# micro-board.net
KiCad netlist of a schematic drawn in EAGLE
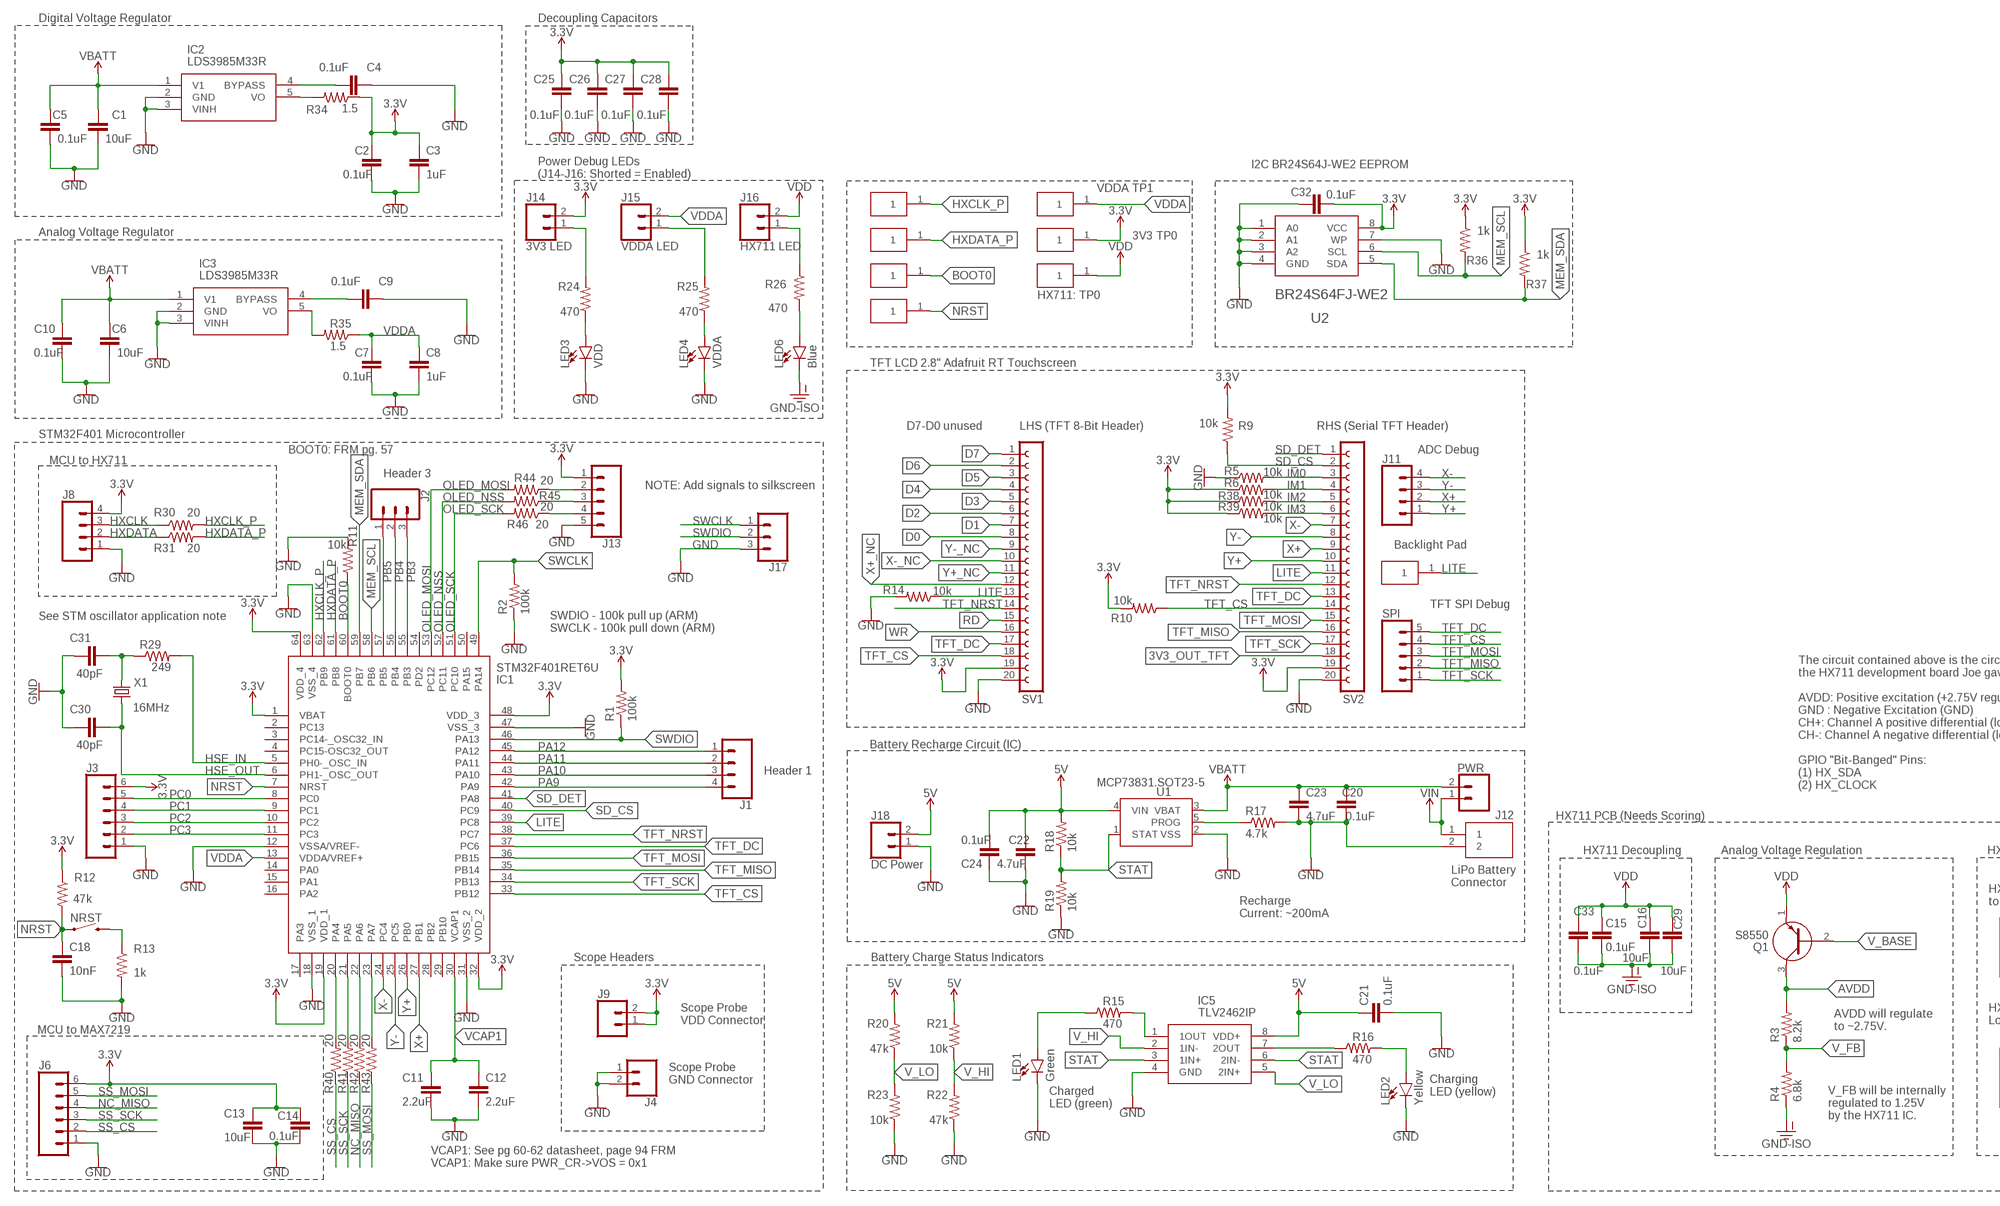
[diagram p0: schematic, sheet 1, part 1 of 2]
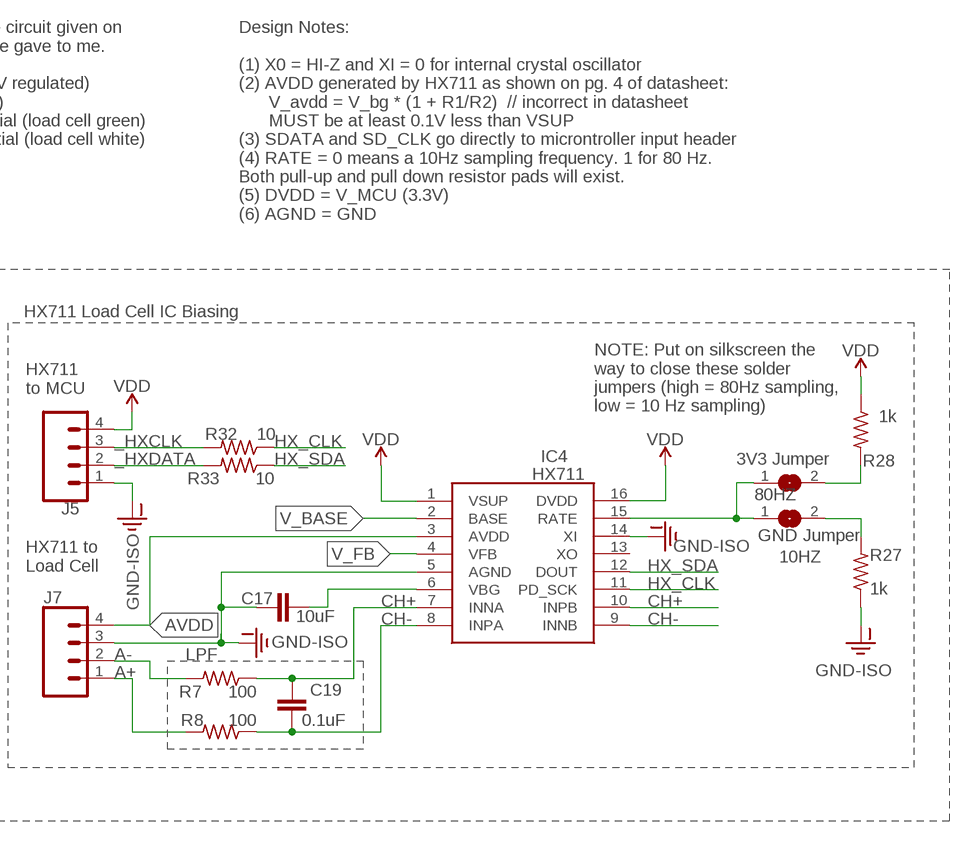
[diagram p1: schematic, sheet 1, part 2 of 2]

(export (version "E")
  (design (tool "Eeschema 10.0.6"))
  (components
    (comp (ref "10HZ")
      (value "GND Jumper")
      (footprint "eagle-import:SJ")
      (libsource (lib "eagle-import") (part "SJ"))
    )
    (comp (ref "80HZ")
      (value "3V3 Jumper")
      (footprint "eagle-import:SJ")
      (libsource (lib "eagle-import") (part "SJ"))
    )
    (comp (ref "C1")
      (value "10uF")
      (footprint "eagle-import:C0603")
      (libsource (lib "eagle-import") (part "CAPACITOR0603"))
    )
    (comp (ref "C2")
      (value "0.1uF")
      (footprint "eagle-import:C0603")
      (libsource (lib "eagle-import") (part "CAPACITOR0603"))
    )
    (comp (ref "C3")
      (value "1uF")
      (footprint "eagle-import:C0603")
      (libsource (lib "eagle-import") (part "CAPACITOR0603"))
    )
    (comp (ref "C4")
      (value "0.1uF")
      (footprint "eagle-import:C0603")
      (libsource (lib "eagle-import") (part "CAPACITOR0603"))
    )
    (comp (ref "C5")
      (value "0.1uF")
      (footprint "eagle-import:C0603")
      (libsource (lib "eagle-import") (part "CAPACITOR0603"))
    )
    (comp (ref "C6")
      (value "10uF")
      (footprint "eagle-import:C0603")
      (libsource (lib "eagle-import") (part "CAPACITOR0603"))
    )
    (comp (ref "C7")
      (value "0.1uF")
      (footprint "eagle-import:C0603")
      (libsource (lib "eagle-import") (part "CAPACITOR0603"))
    )
    (comp (ref "C8")
      (value "1uF")
      (footprint "eagle-import:C0603")
      (libsource (lib "eagle-import") (part "CAPACITOR0603"))
    )
    (comp (ref "C9")
      (value "0.1uF")
      (footprint "eagle-import:C0603")
      (libsource (lib "eagle-import") (part "CAPACITOR0603"))
    )
    (comp (ref "C10")
      (value "0.1uF")
      (footprint "eagle-import:C0603")
      (libsource (lib "eagle-import") (part "CAPACITOR0603"))
    )
    (comp (ref "C11")
      (value "2.2uF")
      (footprint "eagle-import:C0603")
      (libsource (lib "eagle-import") (part "CAPACITOR0603"))
    )
    (comp (ref "C12")
      (value "2.2uF")
      (footprint "eagle-import:C0603")
      (libsource (lib "eagle-import") (part "CAPACITOR0603"))
    )
    (comp (ref "C13")
      (value "10uF")
      (footprint "eagle-import:C0603")
      (libsource (lib "eagle-import") (part "CAPACITOR0603"))
    )
    (comp (ref "C14")
      (value "0.1uF")
      (footprint "eagle-import:C0603")
      (libsource (lib "eagle-import") (part "CAPACITOR0603"))
    )
    (comp (ref "C15")
      (value "0.1uF")
      (footprint "eagle-import:C0603")
      (libsource (lib "eagle-import") (part "CAPACITOR0603"))
    )
    (comp (ref "C16")
      (value "10uF")
      (footprint "eagle-import:C0603")
      (libsource (lib "eagle-import") (part "CAPACITOR0603"))
    )
    (comp (ref "C17")
      (value "10uF")
      (footprint "eagle-import:C0603")
      (libsource (lib "eagle-import") (part "CAPACITOR0603"))
    )
    (comp (ref "C18")
      (value "10nF")
      (footprint "eagle-import:C0603")
      (libsource (lib "eagle-import") (part "CAPACITOR0603"))
    )
    (comp (ref "C19")
      (value "0.1uF")
      (footprint "eagle-import:C0603")
      (libsource (lib "eagle-import") (part "CAPACITOR0603"))
    )
    (comp (ref "C20")
      (value "0.1uF")
      (footprint "eagle-import:C0603")
      (libsource (lib "eagle-import") (part "CAPACITOR0603"))
    )
    (comp (ref "C21")
      (value "0.1uF")
      (footprint "eagle-import:C0603")
      (libsource (lib "eagle-import") (part "CAPACITOR0603"))
    )
    (comp (ref "C22")
      (value "4.7uF")
      (footprint "eagle-import:C5B4.5")
      (libsource (lib "eagle-import") (part "C5/4.5"))
    )
    (comp (ref "C23")
      (value "4.7uF")
      (footprint "eagle-import:C5B4.5")
      (libsource (lib "eagle-import") (part "C5/4.5"))
    )
    (comp (ref "C24")
      (value "0.1uF")
      (footprint "eagle-import:C0603")
      (libsource (lib "eagle-import") (part "CAPACITOR0603"))
    )
    (comp (ref "C25")
      (value "0.1uF")
      (footprint "eagle-import:C0603")
      (libsource (lib "eagle-import") (part "CAPACITOR0603"))
    )
    (comp (ref "C26")
      (value "0.1uF")
      (footprint "eagle-import:C0603")
      (libsource (lib "eagle-import") (part "CAPACITOR0603"))
    )
    (comp (ref "C27")
      (value "0.1uF")
      (footprint "eagle-import:C0603")
      (libsource (lib "eagle-import") (part "CAPACITOR0603"))
    )
    (comp (ref "C28")
      (value "0.1uF")
      (footprint "eagle-import:C0603")
      (libsource (lib "eagle-import") (part "CAPACITOR0603"))
    )
    (comp (ref "C29")
      (value "10uF")
      (footprint "eagle-import:C0603")
      (libsource (lib "eagle-import") (part "CAPACITOR0603"))
    )
    (comp (ref "C30")
      (value "40pF")
      (footprint "eagle-import:C0603")
      (libsource (lib "eagle-import") (part "CAPACITOR0603"))
    )
    (comp (ref "C31")
      (value "40pF")
      (footprint "eagle-import:C0603")
      (libsource (lib "eagle-import") (part "CAPACITOR0603"))
    )
    (comp (ref "C32")
      (value "0.1uF")
      (footprint "eagle-import:C0603")
      (libsource (lib "eagle-import") (part "CAPACITOR0603"))
    )
    (comp (ref "C33")
      (value "0.1uF")
      (footprint "eagle-import:C0603")
      (libsource (lib "eagle-import") (part "CAPACITOR0603"))
    )
    (comp (ref "IC1")
      (value "STM32F401RET6U")
      (footprint "eagle-import:QFP50P1200X1200X160-64N")
      (fields (field (name "MOUSER_PART_NUMBER") "511-STM32F401RET6U"))
      (libsource (lib "eagle-import") (part "STM32F401RET6U"))
    )
    (comp (ref "IC2")
      (value "LDS3985M33R")
      (footprint "eagle-import:SOT95P280X145-5N")
      (fields (field (name "MOUSER_PART_NUMBER") "511-LDS3985M33R"))
      (libsource (lib "eagle-import") (part "LDS3985M33R"))
    )
    (comp (ref "IC3")
      (value "LDS3985M33R")
      (footprint "eagle-import:SOT95P280X145-5N")
      (fields (field (name "MOUSER_PART_NUMBER") "511-LDS3985M33R"))
      (libsource (lib "eagle-import") (part "LDS3985M33R"))
    )
    (comp (ref "IC4")
      (value "HX711")
      (footprint "eagle-import:SOIC127P600X160-16N")
      (libsource (lib "eagle-import") (part "HX711"))
    )
    (comp (ref "IC5")
      (value "TLV2462IP")
      (footprint "eagle-import:DIP794W53P254L959H508Q8N")
      (fields (field (name "MOUSER_PART_NUMBER") "595-TLV2462IP"))
      (libsource (lib "eagle-import") (part "TLV2462IP"))
    )
    (comp (ref "J1")
      (value "CONN_04")
      (footprint "eagle-import:1X04")
      (libsource (lib "eagle-import") (part "CONN_04"))
    )
    (comp (ref "J2")
      (value "CONN_03")
      (footprint "eagle-import:1X03")
      (libsource (lib "eagle-import") (part "CONN_03"))
    )
    (comp (ref "J3")
      (value "CONN_06LOCK")
      (footprint "eagle-import:1X06_LOCK")
      (libsource (lib "eagle-import") (part "CONN_06LOCK"))
    )
    (comp (ref "J4")
      (value "CONN_02")
      (footprint "eagle-import:1X02")
      (libsource (lib "eagle-import") (part "CONN_02"))
    )
    (comp (ref "J5")
      (value "CONN_04")
      (footprint "eagle-import:1X04")
      (libsource (lib "eagle-import") (part "CONN_04"))
    )
    (comp (ref "J6")
      (value "CONN_06SILK_FEMALE_PTH")
      (footprint "eagle-import:1X06")
      (libsource (lib "eagle-import") (part "CONN_06SILK_FEMALE_PTH"))
    )
    (comp (ref "J7")
      (value "CONN_04")
      (footprint "eagle-import:1X04")
      (libsource (lib "eagle-import") (part "CONN_04"))
    )
    (comp (ref "J8")
      (value "CONN_04")
      (footprint "eagle-import:1X04")
      (libsource (lib "eagle-import") (part "CONN_04"))
    )
    (comp (ref "J9")
      (value "CONN_02")
      (footprint "eagle-import:1X02")
      (libsource (lib "eagle-import") (part "CONN_02"))
    )
    (comp (ref "J11")
      (value "CONN_04")
      (footprint "eagle-import:1X04")
      (libsource (lib "eagle-import") (part "CONN_04"))
    )
    (comp (ref "J12")
      (value "B2B-PH-K-S_LF__SN_")
      (footprint "eagle-import:SHDR2W50P0X200_1X2_590X450X600")
      (fields (field (name "ARROW_PART_NUMBER") "B2B-PH-K-S(LF)(SN)"))
      (libsource (lib "eagle-import") (part "B2B-PH-K-S_LF__SN_"))
    )
    (comp (ref "J13")
      (value "CONN_05")
      (footprint "eagle-import:1X05")
      (libsource (lib "eagle-import") (part "CONN_05"))
    )
    (comp (ref "J14")
      (value "3V3 LED")
      (footprint "eagle-import:1X02")
      (libsource (lib "eagle-import") (part "CONN_02"))
    )
    (comp (ref "J15")
      (value "VDDA LED")
      (footprint "eagle-import:1X02")
      (libsource (lib "eagle-import") (part "CONN_02"))
    )
    (comp (ref "J16")
      (value "HX711 LED")
      (footprint "eagle-import:1X02")
      (libsource (lib "eagle-import") (part "CONN_02"))
    )
    (comp (ref "J17")
      (value "CONN_03")
      (footprint "eagle-import:1X03")
      (libsource (lib "eagle-import") (part "CONN_03"))
    )
    (comp (ref "J18")
      (value "DC Power")
      (footprint "eagle-import:1X02")
      (libsource (lib "eagle-import") (part "CONN_02"))
    )
    (comp (ref "LED1")
      (value "Green")
      (footprint "eagle-import:LED-0603")
      (libsource (lib "eagle-import") (part "LED0603"))
    )
    (comp (ref "LED2")
      (value "Yellow")
      (footprint "eagle-import:LED-0603")
      (libsource (lib "eagle-import") (part "LED0603"))
    )
    (comp (ref "LED3")
      (value "VDD")
      (footprint "eagle-import:LED-0603")
      (libsource (lib "eagle-import") (part "LED0603"))
    )
    (comp (ref "LED4")
      (value "VDDA")
      (footprint "eagle-import:LED-0603")
      (libsource (lib "eagle-import") (part "LED0603"))
    )
    (comp (ref "LED6")
      (value "Blue")
      (footprint "eagle-import:LED-0603")
      (libsource (lib "eagle-import") (part "LED0603"))
    )
    (comp (ref "NRST")
      (value "MOMENTARY-SWITCH-SPST-SMD-5.2-REDUNDANT")
      (footprint "eagle-import:TACTILE_SWITCH_SMD_5.2MM")
      (libsource (lib "eagle-import") (part "MOMENTARY-SWITCH-SPST-SMD-5.2-REDUNDANT"))
    )
    (comp (ref "PWR")
      (value "CONN_02")
      (footprint "eagle-import:1X02")
      (libsource (lib "eagle-import") (part "CONN_02"))
    )
    (comp (ref "Q1")
      (value "S8550")
      (footprint "eagle-import:MJE13001TP")
      (libsource (lib "eagle-import") (part "S8550"))
    )
    (comp (ref "R1")
      (value "100k")
      (footprint "eagle-import:R0603")
      (libsource (lib "eagle-import") (part "RESISTOR0603"))
    )
    (comp (ref "R2")
      (value "100k")
      (footprint "eagle-import:R0603")
      (libsource (lib "eagle-import") (part "RESISTOR0603"))
    )
    (comp (ref "R3")
      (value "8.2k")
      (footprint "eagle-import:R0603")
      (libsource (lib "eagle-import") (part "RESISTOR0603"))
    )
    (comp (ref "R4")
      (value "6.8k")
      (footprint "eagle-import:R0603")
      (libsource (lib "eagle-import") (part "RESISTOR0603"))
    )
    (comp (ref "R5")
      (value "10k")
      (footprint "eagle-import:R0603")
      (libsource (lib "eagle-import") (part "RESISTOR0603"))
    )
    (comp (ref "R6")
      (value "10k")
      (footprint "eagle-import:R0603")
      (libsource (lib "eagle-import") (part "RESISTOR0603"))
    )
    (comp (ref "R7")
      (value "100")
      (footprint "eagle-import:R0603")
      (libsource (lib "eagle-import") (part "RESISTOR0603"))
    )
    (comp (ref "R8")
      (value "100")
      (footprint "eagle-import:R0603")
      (libsource (lib "eagle-import") (part "RESISTOR0603"))
    )
    (comp (ref "R9")
      (value "10k")
      (footprint "eagle-import:R0603")
      (libsource (lib "eagle-import") (part "RESISTOR0603"))
    )
    (comp (ref "R10")
      (value "10k")
      (footprint "eagle-import:R0603")
      (libsource (lib "eagle-import") (part "RESISTOR0603"))
    )
    (comp (ref "R11")
      (value "10k")
      (footprint "eagle-import:R0603")
      (libsource (lib "eagle-import") (part "RESISTOR0603"))
    )
    (comp (ref "R12")
      (value "47k")
      (footprint "eagle-import:R0603")
      (libsource (lib "eagle-import") (part "RESISTOR0603"))
    )
    (comp (ref "R13")
      (value "1k")
      (footprint "eagle-import:R0603")
      (libsource (lib "eagle-import") (part "RESISTOR0603"))
    )
    (comp (ref "R14")
      (value "10k")
      (footprint "eagle-import:R0603")
      (libsource (lib "eagle-import") (part "RESISTOR0603"))
    )
    (comp (ref "R15")
      (value "470")
      (footprint "eagle-import:R0603")
      (libsource (lib "eagle-import") (part "RESISTOR0603"))
    )
    (comp (ref "R16")
      (value "470")
      (footprint "eagle-import:R0603")
      (libsource (lib "eagle-import") (part "RESISTOR0603"))
    )
    (comp (ref "R17")
      (value "4.7k")
      (footprint "eagle-import:R0603")
      (libsource (lib "eagle-import") (part "RESISTOR0603"))
    )
    (comp (ref "R18")
      (value "10k")
      (footprint "eagle-import:R0603")
      (libsource (lib "eagle-import") (part "RESISTOR0603"))
    )
    (comp (ref "R19")
      (value "10k")
      (footprint "eagle-import:R0603")
      (libsource (lib "eagle-import") (part "RESISTOR0603"))
    )
    (comp (ref "R20")
      (value "47k")
      (footprint "eagle-import:R0603")
      (libsource (lib "eagle-import") (part "RESISTOR0603"))
    )
    (comp (ref "R21")
      (value "10k")
      (footprint "eagle-import:R0603")
      (libsource (lib "eagle-import") (part "RESISTOR0603"))
    )
    (comp (ref "R22")
      (value "47k")
      (footprint "eagle-import:R0603")
      (libsource (lib "eagle-import") (part "RESISTOR0603"))
    )
    (comp (ref "R23")
      (value "10k")
      (footprint "eagle-import:R0603")
      (libsource (lib "eagle-import") (part "RESISTOR0603"))
    )
    (comp (ref "R24")
      (value "470")
      (footprint "eagle-import:R0603")
      (libsource (lib "eagle-import") (part "RESISTOR0603"))
    )
    (comp (ref "R25")
      (value "470")
      (footprint "eagle-import:R0603")
      (libsource (lib "eagle-import") (part "RESISTOR0603"))
    )
    (comp (ref "R26")
      (value "470")
      (footprint "eagle-import:R0603")
      (libsource (lib "eagle-import") (part "RESISTOR0603"))
    )
    (comp (ref "R27")
      (value "1k")
      (footprint "eagle-import:R0603")
      (libsource (lib "eagle-import") (part "RESISTOR0603"))
    )
    (comp (ref "R28")
      (value "1k")
      (footprint "eagle-import:R0603")
      (libsource (lib "eagle-import") (part "RESISTOR0603"))
    )
    (comp (ref "R29")
      (value "249")
      (footprint "eagle-import:R0603")
      (libsource (lib "eagle-import") (part "RESISTOR0603"))
    )
    (comp (ref "R30")
      (value "20")
      (footprint "eagle-import:R0603")
      (libsource (lib "eagle-import") (part "RESISTOR0603"))
    )
    (comp (ref "R31")
      (value "20")
      (footprint "eagle-import:R0603")
      (libsource (lib "eagle-import") (part "RESISTOR0603"))
    )
    (comp (ref "R32")
      (value "10")
      (footprint "eagle-import:R0603")
      (libsource (lib "eagle-import") (part "RESISTOR0603"))
    )
    (comp (ref "R33")
      (value "10")
      (footprint "eagle-import:R0603")
      (libsource (lib "eagle-import") (part "RESISTOR0603"))
    )
    (comp (ref "R34")
      (value "1.5")
      (footprint "eagle-import:R0603")
      (libsource (lib "eagle-import") (part "RESISTOR0603"))
    )
    (comp (ref "R35")
      (value "1.5")
      (footprint "eagle-import:R0603")
      (libsource (lib "eagle-import") (part "RESISTOR0603"))
    )
    (comp (ref "R36")
      (value "1k")
      (footprint "eagle-import:R0603")
      (libsource (lib "eagle-import") (part "RESISTOR0603"))
    )
    (comp (ref "R37")
      (value "1k")
      (footprint "eagle-import:R0603")
      (libsource (lib "eagle-import") (part "RESISTOR0603"))
    )
    (comp (ref "R38")
      (value "10k")
      (footprint "eagle-import:R0603")
      (libsource (lib "eagle-import") (part "RESISTOR0603"))
    )
    (comp (ref "R39")
      (value "10k")
      (footprint "eagle-import:R0603")
      (libsource (lib "eagle-import") (part "RESISTOR0603"))
    )
    (comp (ref "R40")
      (value "20")
      (footprint "eagle-import:R0603")
      (libsource (lib "eagle-import") (part "RESISTOR0603"))
    )
    (comp (ref "R41")
      (value "20")
      (footprint "eagle-import:R0603")
      (libsource (lib "eagle-import") (part "RESISTOR0603"))
    )
    (comp (ref "R42")
      (value "20")
      (footprint "eagle-import:R0603")
      (libsource (lib "eagle-import") (part "RESISTOR0603"))
    )
    (comp (ref "R43")
      (value "20")
      (footprint "eagle-import:R0603")
      (libsource (lib "eagle-import") (part "RESISTOR0603"))
    )
    (comp (ref "R44")
      (value "20")
      (footprint "eagle-import:R0603")
      (libsource (lib "eagle-import") (part "RESISTOR0603"))
    )
    (comp (ref "R45")
      (value "20")
      (footprint "eagle-import:R0603")
      (libsource (lib "eagle-import") (part "RESISTOR0603"))
    )
    (comp (ref "R46")
      (value "20")
      (footprint "eagle-import:R0603")
      (libsource (lib "eagle-import") (part "RESISTOR0603"))
    )
    (comp (ref "SPI")
      (value "CONN_05")
      (footprint "eagle-import:1X05")
      (libsource (lib "eagle-import") (part "CONN_05"))
    )
    (comp (ref "SV1")
      (value "LHS (TFT 8-Bit Header)")
      (footprint "eagle-import:FE20")
      (libsource (lib "eagle-import") (part "FE20-1"))
    )
    (comp (ref "SV2")
      (value "RHS (Serial TFT Header)")
      (footprint "eagle-import:FE20")
      (libsource (lib "eagle-import") (part "FE20-1"))
    )
    (comp (ref "U$1")
      (value "TP1")
      (footprint "eagle-import:PAD")
      (libsource (lib "eagle-import") (part "PAD"))
    )
    (comp (ref "U$2")
      (value "TP3")
      (footprint "eagle-import:PAD")
      (libsource (lib "eagle-import") (part "PAD"))
    )
    (comp (ref "U$3")
      (value "TP4")
      (footprint "eagle-import:PAD")
      (libsource (lib "eagle-import") (part "PAD"))
    )
    (comp (ref "U$4")
      (value "TP5")
      (footprint "eagle-import:PAD")
      (libsource (lib "eagle-import") (part "PAD"))
    )
    (comp (ref "U$5")
      (value "TP6")
      (footprint "eagle-import:PAD")
      (libsource (lib "eagle-import") (part "PAD"))
    )
    (comp (ref "U$6")
      (value "TP1")
      (footprint "eagle-import:PAD")
      (libsource (lib "eagle-import") (part "PAD"))
    )
    (comp (ref "U$7")
      (value "TP0")
      (footprint "eagle-import:PAD")
      (libsource (lib "eagle-import") (part "PAD"))
    )
    (comp (ref "U$8")
      (value "TP2")
      (footprint "eagle-import:PAD")
      (libsource (lib "eagle-import") (part "PAD"))
    )
    (comp (ref "U1")
      (value "MCP73831.SOT23-5")
      (footprint "eagle-import:SOT23-5")
      (libsource (lib "eagle-import") (part "MCP73831.SOT23-5"))
    )
    (comp (ref "U2")
      (value "BR24S64FJ-WE2")
      (footprint "eagle-import:SOIC8")
      (libsource (lib "eagle-import") (part "BR24S64FJ-WE2"))
    )
    (comp (ref "X1")
      (value "16MHz")
      (footprint "eagle-import:HC49_S")
      (libsource (lib "eagle-import") (part "CRYSTALHC49S"))
    )
  )
  (nets
    (net (code "1") (name "/A+") (class "Default")
      (node (ref "J7") (pin "1") (pinfunction "1_1") (pintype "passive"))
      (node (ref "R8") (pin "2") (pinfunction "2_2") (pintype "passive"))
    )
    (net (code "2") (name "/A-") (class "Default")
      (node (ref "J7") (pin "2") (pinfunction "2_2") (pintype "passive"))
      (node (ref "R7") (pin "2") (pinfunction "2_2") (pintype "passive"))
    )
    (net (code "3") (name "/CH+") (class "Default")
      (node (ref "C19") (pin "1") (pinfunction "1_1") (pintype "passive"))
      (node (ref "IC4") (pin "10") (pinfunction "INPB_10") (pintype "bidirectional"))
      (node (ref "IC4") (pin "7") (pinfunction "INNA_7") (pintype "bidirectional"))
      (node (ref "R7") (pin "1") (pinfunction "1_1") (pintype "passive"))
    )
    (net (code "4") (name "/CH-") (class "Default")
      (node (ref "C19") (pin "2") (pinfunction "2_2") (pintype "passive"))
      (node (ref "IC4") (pin "8") (pinfunction "INPA_8") (pintype "bidirectional"))
      (node (ref "IC4") (pin "9") (pinfunction "INNB_9") (pintype "bidirectional"))
      (node (ref "R8") (pin "1") (pinfunction "1_1") (pintype "passive"))
    )
    (net (code "5") (name "/HSE_IN") (class "Default")
      (node (ref "IC1") (pin "5") (pinfunction "PH0-_OSC_IN_5") (pintype "bidirectional"))
      (node (ref "R29") (pin "2") (pinfunction "2_2") (pintype "passive"))
    )
    (net (code "6") (name "/HSE_OUT") (class "Default")
      (node (ref "C30") (pin "2") (pinfunction "2_2") (pintype "passive"))
      (node (ref "IC1") (pin "6") (pinfunction "PH1-_OSC_OUT_6") (pintype "bidirectional"))
      (node (ref "X1") (pin "1") (pinfunction "1_1") (pintype "passive"))
    )
    (net (code "7") (name "/HXCLK") (class "Default")
      (node (ref "J8") (pin "3") (pinfunction "3_3") (pintype "passive"))
      (node (ref "R30") (pin "1") (pinfunction "1_1") (pintype "passive"))
    )
    (net (code "8") (name "/HXDATA") (class "Default")
      (node (ref "J8") (pin "2") (pinfunction "2_2") (pintype "passive"))
      (node (ref "R31") (pin "1") (pinfunction "1_1") (pintype "passive"))
    )
    (net (code "9") (name "/HX_CLK") (class "Default")
      (node (ref "IC4") (pin "11") (pinfunction "PD_SCK_11") (pintype "bidirectional"))
      (node (ref "R32") (pin "1") (pinfunction "1_1") (pintype "passive"))
    )
    (net (code "10") (name "/HX_SDA") (class "Default")
      (node (ref "IC4") (pin "12") (pinfunction "DOUT_12") (pintype "bidirectional"))
      (node (ref "R33") (pin "1") (pinfunction "1_1") (pintype "passive"))
    )
    (net (code "11") (name "/IM0") (class "Default")
      (node (ref "R5") (pin "2") (pinfunction "2_2") (pintype "passive"))
      (node (ref "SV2") (pin "3") (pinfunction "3_3") (pintype "passive"))
    )
    (net (code "12") (name "/IM1") (class "Default")
      (node (ref "R6") (pin "2") (pinfunction "2_2") (pintype "passive"))
      (node (ref "SV2") (pin "4") (pinfunction "4_4") (pintype "passive"))
    )
    (net (code "13") (name "/IM2") (class "Default")
      (node (ref "R38") (pin "2") (pinfunction "2_2") (pintype "passive"))
      (node (ref "SV2") (pin "5") (pinfunction "5_5") (pintype "passive"))
    )
    (net (code "14") (name "/IM3") (class "Default")
      (node (ref "R39") (pin "2") (pinfunction "2_2") (pintype "passive"))
      (node (ref "SV2") (pin "6") (pinfunction "6_6") (pintype "passive"))
    )
    (net (code "15") (name "/NC_MISO") (class "Default")
      (node (ref "J6") (pin "4") (pinfunction "4_4") (pintype "passive"))
      (node (ref "R42") (pin "1") (pinfunction "1_1") (pintype "passive"))
    )
    (net (code "16") (name "/OLED_MOSI") (class "Default")
      (node (ref "IC1") (pin "53") (pinfunction "PC12_53") (pintype "bidirectional"))
      (node (ref "R44") (pin "2") (pinfunction "2_2") (pintype "passive"))
    )
    (net (code "17") (name "/OLED_NSS") (class "Default")
      (node (ref "IC1") (pin "52") (pinfunction "PC11_52") (pintype "bidirectional"))
      (node (ref "R45") (pin "2") (pinfunction "2_2") (pintype "passive"))
    )
    (net (code "18") (name "/OLED_SCK") (class "Default")
      (node (ref "IC1") (pin "51") (pinfunction "PC10_51") (pintype "bidirectional"))
      (node (ref "R46") (pin "2") (pinfunction "2_2") (pintype "passive"))
    )
    (net (code "19") (name "/PA9") (class "Default")
      (node (ref "IC1") (pin "42") (pinfunction "PA9_42") (pintype "bidirectional"))
      (node (ref "J1") (pin "4") (pinfunction "4_4") (pintype "passive"))
    )
    (net (code "20") (name "/PA10") (class "Default")
      (node (ref "IC1") (pin "43") (pinfunction "PA10_43") (pintype "bidirectional"))
      (node (ref "J1") (pin "3") (pinfunction "3_3") (pintype "passive"))
    )
    (net (code "21") (name "/PA11") (class "Default")
      (node (ref "IC1") (pin "44") (pinfunction "PA11_44") (pintype "bidirectional"))
      (node (ref "J1") (pin "2") (pinfunction "2_2") (pintype "passive"))
    )
    (net (code "22") (name "/PA12") (class "Default")
      (node (ref "IC1") (pin "45") (pinfunction "PA12_45") (pintype "bidirectional"))
      (node (ref "J1") (pin "1") (pinfunction "1_1") (pintype "passive"))
    )
    (net (code "23") (name "/PB3") (class "Default")
      (node (ref "IC1") (pin "55") (pinfunction "PB3_55") (pintype "bidirectional"))
      (node (ref "J2") (pin "3") (pinfunction "3_3") (pintype "passive"))
    )
    (net (code "24") (name "/PB4") (class "Default")
      (node (ref "IC1") (pin "56") (pinfunction "PB4_56") (pintype "bidirectional"))
      (node (ref "J2") (pin "2") (pinfunction "2_2") (pintype "passive"))
    )
    (net (code "25") (name "/PB5") (class "Default")
      (node (ref "IC1") (pin "57") (pinfunction "PB5_57") (pintype "bidirectional"))
      (node (ref "J2") (pin "1") (pinfunction "1_1") (pintype "passive"))
    )
    (net (code "26") (name "/PC0") (class "Default")
      (node (ref "IC1") (pin "8") (pinfunction "PC0_8") (pintype "bidirectional"))
      (node (ref "J3") (pin "5") (pinfunction "5_5") (pintype "passive"))
    )
    (net (code "27") (name "/PC1") (class "Default")
      (node (ref "IC1") (pin "9") (pinfunction "PC1_9") (pintype "bidirectional"))
      (node (ref "J3") (pin "4") (pinfunction "4_4") (pintype "passive"))
    )
    (net (code "28") (name "/PC2") (class "Default")
      (node (ref "IC1") (pin "10") (pinfunction "PC2_10") (pintype "bidirectional"))
      (node (ref "J3") (pin "3") (pinfunction "3_3") (pintype "passive"))
    )
    (net (code "29") (name "/PC3") (class "Default")
      (node (ref "IC1") (pin "11") (pinfunction "PC3_11") (pintype "bidirectional"))
      (node (ref "J3") (pin "2") (pinfunction "2_2") (pintype "passive"))
    )
    (net (code "30") (name "/SS_CS") (class "Default")
      (node (ref "J6") (pin "2") (pinfunction "2_2") (pintype "passive"))
      (node (ref "R40") (pin "1") (pinfunction "1_1") (pintype "passive"))
    )
    (net (code "31") (name "/SS_MOSI") (class "Default")
      (node (ref "J6") (pin "5") (pinfunction "5_5") (pintype "passive"))
      (node (ref "R43") (pin "1") (pinfunction "1_1") (pintype "passive"))
    )
    (net (code "32") (name "/SS_SCK") (class "Default")
      (node (ref "J6") (pin "3") (pinfunction "3_3") (pintype "passive"))
      (node (ref "R41") (pin "1") (pinfunction "1_1") (pintype "passive"))
    )
    (net (code "33") (name "/_HXCLK") (class "Default")
      (node (ref "J5") (pin "3") (pinfunction "3_3") (pintype "passive"))
      (node (ref "R32") (pin "2") (pinfunction "2_2") (pintype "passive"))
    )
    (net (code "34") (name "/_HXDATA") (class "Default")
      (node (ref "J5") (pin "2") (pinfunction "2_2") (pintype "passive"))
      (node (ref "R33") (pin "2") (pinfunction "2_2") (pintype "passive"))
    )
    (net (code "35") (name "3.3V") (class "Default")
      (node (ref "C13") (pin "1") (pinfunction "1_1") (pintype "passive"))
      (node (ref "C14") (pin "1") (pinfunction "1_1") (pintype "passive"))
      (node (ref "C2") (pin "1") (pinfunction "1_1") (pintype "passive"))
      (node (ref "C25") (pin "1") (pinfunction "1_1") (pintype "passive"))
      (node (ref "C26") (pin "1") (pinfunction "1_1") (pintype "passive"))
      (node (ref "C27") (pin "1") (pinfunction "1_1") (pintype "passive"))
      (node (ref "C28") (pin "1") (pinfunction "1_1") (pintype "passive"))
      (node (ref "C3") (pin "1") (pinfunction "1_1") (pintype "passive"))
      (node (ref "C32") (pin "2") (pinfunction "2_2") (pintype "passive"))
      (node (ref "IC1") (pin "1") (pinfunction "VBAT_1") (pintype "bidirectional"))
      (node (ref "IC1") (pin "19") (pinfunction "VDD_1_19") (pintype "bidirectional"))
      (node (ref "IC1") (pin "32") (pinfunction "VDD_2_32") (pintype "bidirectional"))
      (node (ref "IC1") (pin "48") (pinfunction "VDD_3_48") (pintype "bidirectional"))
      (node (ref "IC1") (pin "64") (pinfunction "VDD_4_64") (pintype "bidirectional"))
      (node (ref "J13") (pin "1") (pinfunction "1_1") (pintype "passive"))
      (node (ref "J14") (pin "2") (pinfunction "2_2") (pintype "passive"))
      (node (ref "J3") (pin "6") (pinfunction "6_6") (pintype "passive"))
      (node (ref "J6") (pin "6") (pinfunction "6_6") (pintype "passive"))
      (node (ref "J8") (pin "4") (pinfunction "4_4") (pintype "passive"))
      (node (ref "J9") (pin "1") (pinfunction "1_1") (pintype "passive"))
      (node (ref "J9") (pin "2") (pinfunction "2_2") (pintype "passive"))
      (node (ref "R1") (pin "2") (pinfunction "2_2") (pintype "passive"))
      (node (ref "R10") (pin "2") (pinfunction "2_2") (pintype "passive"))
      (node (ref "R12") (pin "1") (pinfunction "1_1") (pintype "passive"))
      (node (ref "R34") (pin "1") (pinfunction "1_1") (pintype "passive"))
      (node (ref "R36") (pin "1") (pinfunction "1_1") (pintype "passive"))
      (node (ref "R37") (pin "1") (pinfunction "1_1") (pintype "passive"))
      (node (ref "R38") (pin "1") (pinfunction "1_1") (pintype "passive"))
      (node (ref "R39") (pin "1") (pinfunction "1_1") (pintype "passive"))
      (node (ref "R6") (pin "1") (pinfunction "1_1") (pintype "passive"))
      (node (ref "R9") (pin "2") (pinfunction "2_2") (pintype "passive"))
      (node (ref "SV1") (pin "19") (pinfunction "19_19") (pintype "passive"))
      (node (ref "SV2") (pin "19") (pinfunction "19_19") (pintype "passive"))
      (node (ref "U$7") (pin "1") (pinfunction "1_1") (pintype "bidirectional"))
      (node (ref "U2") (pin "8") (pinfunction "VCC_8") (pintype "power_in"))
    )
    (net (code "36") (name "3V3_OUT_TFT") (class "Default")
      (node (ref "SV2") (pin "18") (pinfunction "18_18") (pintype "passive"))
    )
    (net (code "37") (name "5V") (class "Default")
      (node (ref "C21") (pin "1") (pinfunction "1_1") (pintype "passive"))
      (node (ref "C22") (pin "1") (pinfunction "1_1") (pintype "passive"))
      (node (ref "C24") (pin "2") (pinfunction "2_2") (pintype "passive"))
      (node (ref "IC5") (pin "8") (pinfunction "VDD+_8") (pintype "bidirectional"))
      (node (ref "J18") (pin "2") (pinfunction "2_2") (pintype "passive"))
      (node (ref "R18") (pin "2") (pinfunction "2_2") (pintype "passive"))
      (node (ref "R20") (pin "2") (pinfunction "2_2") (pintype "passive"))
      (node (ref "R21") (pin "2") (pinfunction "2_2") (pintype "passive"))
      (node (ref "U1") (pin "4") (pinfunction "VIN_4") (pintype "power_in"))
    )
    (net (code "38") (name "AVDD") (class "Default")
      (node (ref "IC4") (pin "3") (pinfunction "AVDD_3") (pintype "bidirectional"))
      (node (ref "J7") (pin "4") (pinfunction "4_4") (pintype "passive"))
      (node (ref "Q1") (pin "3") (pinfunction "C_3") (pintype "bidirectional"))
      (node (ref "R3") (pin "2") (pinfunction "2_2") (pintype "passive"))
    )
    (net (code "39") (name "BOOT0") (class "Default")
      (node (ref "IC1") (pin "60") (pinfunction "BOOT0_60") (pintype "bidirectional"))
      (node (ref "R11") (pin "1") (pinfunction "1_1") (pintype "passive"))
      (node (ref "U$4") (pin "1") (pinfunction "1_1") (pintype "bidirectional"))
    )
    (net (code "40") (name "D0") (class "Default")
      (node (ref "SV1") (pin "8") (pinfunction "8_8") (pintype "passive"))
    )
    (net (code "41") (name "D1") (class "Default")
      (node (ref "SV1") (pin "7") (pinfunction "7_7") (pintype "passive"))
    )
    (net (code "42") (name "D2") (class "Default")
      (node (ref "SV1") (pin "6") (pinfunction "6_6") (pintype "passive"))
    )
    (net (code "43") (name "D3") (class "Default")
      (node (ref "SV1") (pin "5") (pinfunction "5_5") (pintype "passive"))
    )
    (net (code "44") (name "D4") (class "Default")
      (node (ref "SV1") (pin "4") (pinfunction "4_4") (pintype "passive"))
    )
    (net (code "45") (name "D5") (class "Default")
      (node (ref "SV1") (pin "3") (pinfunction "3_3") (pintype "passive"))
    )
    (net (code "46") (name "D6") (class "Default")
      (node (ref "SV1") (pin "2") (pinfunction "2_2") (pintype "passive"))
    )
    (net (code "47") (name "D7") (class "Default")
      (node (ref "SV1") (pin "1") (pinfunction "1_1") (pintype "passive"))
    )
    (net (code "48") (name "GND") (class "Default")
      (node (ref "C1") (pin "2") (pinfunction "2_2") (pintype "passive"))
      (node (ref "C10") (pin "2") (pinfunction "2_2") (pintype "passive"))
      (node (ref "C11") (pin "2") (pinfunction "2_2") (pintype "passive"))
      (node (ref "C12") (pin "2") (pinfunction "2_2") (pintype "passive"))
      (node (ref "C13") (pin "2") (pinfunction "2_2") (pintype "passive"))
      (node (ref "C14") (pin "2") (pinfunction "2_2") (pintype "passive"))
      (node (ref "C18") (pin "2") (pinfunction "2_2") (pintype "passive"))
      (node (ref "C2") (pin "2") (pinfunction "2_2") (pintype "passive"))
      (node (ref "C20") (pin "2") (pinfunction "2_2") (pintype "passive"))
      (node (ref "C21") (pin "2") (pinfunction "2_2") (pintype "passive"))
      (node (ref "C22") (pin "2") (pinfunction "2_2") (pintype "passive"))
      (node (ref "C23") (pin "2") (pinfunction "2_2") (pintype "passive"))
      (node (ref "C24") (pin "1") (pinfunction "1_1") (pintype "passive"))
      (node (ref "C25") (pin "2") (pinfunction "2_2") (pintype "passive"))
      (node (ref "C26") (pin "2") (pinfunction "2_2") (pintype "passive"))
      (node (ref "C27") (pin "2") (pinfunction "2_2") (pintype "passive"))
      (node (ref "C28") (pin "2") (pinfunction "2_2") (pintype "passive"))
      (node (ref "C3") (pin "2") (pinfunction "2_2") (pintype "passive"))
      (node (ref "C30") (pin "1") (pinfunction "1_1") (pintype "passive"))
      (node (ref "C31") (pin "1") (pinfunction "1_1") (pintype "passive"))
      (node (ref "C32") (pin "1") (pinfunction "1_1") (pintype "passive"))
      (node (ref "C4") (pin "1") (pinfunction "1_1") (pintype "passive"))
      (node (ref "C5") (pin "2") (pinfunction "2_2") (pintype "passive"))
      (node (ref "C6") (pin "2") (pinfunction "2_2") (pintype "passive"))
      (node (ref "C7") (pin "2") (pinfunction "2_2") (pintype "passive"))
      (node (ref "C8") (pin "2") (pinfunction "2_2") (pintype "passive"))
      (node (ref "C9") (pin "1") (pinfunction "1_1") (pintype "passive"))
      (node (ref "IC1") (pin "12") (pinfunction "VSSA/VREF-_12") (pintype "bidirectional"))
      (node (ref "IC1") (pin "18") (pinfunction "VSS_1_18") (pintype "bidirectional"))
      (node (ref "IC1") (pin "31") (pinfunction "VSS_2_31") (pintype "bidirectional"))
      (node (ref "IC1") (pin "47") (pinfunction "VSS_3_47") (pintype "bidirectional"))
      (node (ref "IC1") (pin "63") (pinfunction "VSS_4_63") (pintype "bidirectional"))
      (node (ref "IC2") (pin "2") (pinfunction "GND_2") (pintype "bidirectional"))
      (node (ref "IC2") (pin "3") (pinfunction "VINH_3") (pintype "bidirectional"))
      (node (ref "IC3") (pin "2") (pinfunction "GND_2") (pintype "bidirectional"))
      (node (ref "IC3") (pin "3") (pinfunction "VINH_3") (pintype "bidirectional"))
      (node (ref "IC5") (pin "4") (pinfunction "GND_4") (pintype "bidirectional"))
      (node (ref "J12") (pin "2") (pinfunction "2_2") (pintype "bidirectional"))
      (node (ref "J13") (pin "5") (pinfunction "5_5") (pintype "passive"))
      (node (ref "J17") (pin "3") (pinfunction "3_3") (pintype "passive"))
      (node (ref "J18") (pin "1") (pinfunction "1_1") (pintype "passive"))
      (node (ref "J3") (pin "1") (pinfunction "1_1") (pintype "passive"))
      (node (ref "J4") (pin "1") (pinfunction "1_1") (pintype "passive"))
      (node (ref "J4") (pin "2") (pinfunction "2_2") (pintype "passive"))
      (node (ref "J6") (pin "1") (pinfunction "1_1") (pintype "passive"))
      (node (ref "J8") (pin "1") (pinfunction "1_1") (pintype "passive"))
      (node (ref "LED1") (pin "C") (pinfunction "C_C") (pintype "passive"))
      (node (ref "LED2") (pin "C") (pinfunction "C_C") (pintype "passive"))
      (node (ref "LED3") (pin "C") (pinfunction "C_C") (pintype "passive"))
      (node (ref "LED4") (pin "C") (pinfunction "C_C") (pintype "passive"))
      (node (ref "R11") (pin "2") (pinfunction "2_2") (pintype "passive"))
      (node (ref "R13") (pin "2") (pinfunction "2_2") (pintype "passive"))
      (node (ref "R14") (pin "2") (pinfunction "2_2") (pintype "passive"))
      (node (ref "R17") (pin "2") (pinfunction "2_2") (pintype "passive"))
      (node (ref "R19") (pin "1") (pinfunction "1_1") (pintype "passive"))
      (node (ref "R2") (pin "1") (pinfunction "1_1") (pintype "passive"))
      (node (ref "R22") (pin "1") (pinfunction "1_1") (pintype "passive"))
      (node (ref "R23") (pin "1") (pinfunction "1_1") (pintype "passive"))
      (node (ref "R5") (pin "1") (pinfunction "1_1") (pintype "passive"))
      (node (ref "SV1") (pin "20") (pinfunction "20_20") (pintype "passive"))
      (node (ref "SV2") (pin "20") (pinfunction "20_20") (pintype "passive"))
      (node (ref "U1") (pin "2") (pinfunction "VSS_2") (pintype "power_in"))
      (node (ref "U2") (pin "1") (pinfunction "A0_1") (pintype "bidirectional"))
      (node (ref "U2") (pin "2") (pinfunction "A1_2") (pintype "bidirectional"))
      (node (ref "U2") (pin "3") (pinfunction "A2_3") (pintype "bidirectional"))
      (node (ref "U2") (pin "4") (pinfunction "GND_4") (pintype "power_in"))
      (node (ref "U2") (pin "7") (pinfunction "WP_7") (pintype "bidirectional"))
    )
    (net (code "49") (name "GND-ISO") (class "Default")
      (node (ref "C15") (pin "2") (pinfunction "2_2") (pintype "passive"))
      (node (ref "C16") (pin "2") (pinfunction "2_2") (pintype "passive"))
      (node (ref "C17") (pin "1") (pinfunction "1_1") (pintype "passive"))
      (node (ref "C29") (pin "2") (pinfunction "2_2") (pintype "passive"))
      (node (ref "C33") (pin "2") (pinfunction "2_2") (pintype "passive"))
      (node (ref "IC4") (pin "14") (pinfunction "XI_14") (pintype "bidirectional"))
      (node (ref "IC4") (pin "5") (pinfunction "AGND_5") (pintype "bidirectional"))
      (node (ref "J5") (pin "1") (pinfunction "1_1") (pintype "passive"))
      (node (ref "J7") (pin "3") (pinfunction "3_3") (pintype "passive"))
      (node (ref "LED6") (pin "C") (pinfunction "C_C") (pintype "passive"))
      (node (ref "R27") (pin "1") (pinfunction "1_1") (pintype "passive"))
      (node (ref "R4") (pin "1") (pinfunction "1_1") (pintype "passive"))
    )
    (net (code "50") (name "HXCLK_P") (class "Default")
      (node (ref "IC1") (pin "62") (pinfunction "PB9_62") (pintype "bidirectional"))
      (node (ref "R30") (pin "2") (pinfunction "2_2") (pintype "passive"))
      (node (ref "U$2") (pin "1") (pinfunction "1_1") (pintype "bidirectional"))
    )
    (net (code "51") (name "HXDATA_P") (class "Default")
      (node (ref "IC1") (pin "61") (pinfunction "PB8_61") (pintype "bidirectional"))
      (node (ref "R31") (pin "2") (pinfunction "2_2") (pintype "passive"))
      (node (ref "U$3") (pin "1") (pinfunction "1_1") (pintype "bidirectional"))
    )
    (net (code "52") (name "LITE") (class "Default")
      (node (ref "IC1") (pin "39") (pinfunction "PC8_39") (pintype "bidirectional"))
      (node (ref "R14") (pin "1") (pinfunction "1_1") (pintype "passive"))
      (node (ref "SV1") (pin "13") (pinfunction "13_13") (pintype "passive"))
      (node (ref "SV2") (pin "11") (pinfunction "11_11") (pintype "passive"))
      (node (ref "U$1") (pin "1") (pinfunction "1_1") (pintype "bidirectional"))
    )
    (net (code "53") (name "MEM_SCL") (class "Default")
      (node (ref "IC1") (pin "58") (pinfunction "PB6_58") (pintype "bidirectional"))
      (node (ref "R36") (pin "2") (pinfunction "2_2") (pintype "passive"))
      (node (ref "U2") (pin "6") (pinfunction "SCL_6") (pintype "bidirectional"))
    )
    (net (code "54") (name "MEM_SDA") (class "Default")
      (node (ref "IC1") (pin "59") (pinfunction "PB7_59") (pintype "bidirectional"))
      (node (ref "R37") (pin "2") (pinfunction "2_2") (pintype "passive"))
      (node (ref "U2") (pin "5") (pinfunction "SDA_5") (pintype "bidirectional"))
    )
    (net (code "55") (name "NRST") (class "Default")
      (node (ref "C18") (pin "1") (pinfunction "1_1") (pintype "passive"))
      (node (ref "IC1") (pin "7") (pinfunction "NRST_7") (pintype "bidirectional"))
      (node (ref "NRST") (pin "1") (pinfunction "1_1") (pintype "passive"))
      (node (ref "NRST") (pin "2") (pinfunction "1_2") (pintype "passive"))
      (node (ref "R12") (pin "2") (pinfunction "2_2") (pintype "passive"))
      (node (ref "U$5") (pin "1") (pinfunction "1_1") (pintype "bidirectional"))
    )
    (net (code "56") (name "Net-(10HZ-Pad2)") (class "Default")
      (node (ref "10HZ") (pin "2") (pinfunction "2_2") (pintype "passive"))
      (node (ref "R27") (pin "2") (pinfunction "2_2") (pintype "passive"))
    )
    (net (code "57") (name "Net-(80HZ-Pad2)") (class "Default")
      (node (ref "80HZ") (pin "2") (pinfunction "2_2") (pintype "passive"))
      (node (ref "R28") (pin "2") (pinfunction "2_2") (pintype "passive"))
    )
    (net (code "58") (name "Net-(C31-Pad2)") (class "Default")
      (node (ref "C31") (pin "2") (pinfunction "2_2") (pintype "passive"))
      (node (ref "R29") (pin "1") (pinfunction "1_1") (pintype "passive"))
      (node (ref "X1") (pin "2") (pinfunction "2_2") (pintype "passive"))
    )
    (net (code "59") (name "Net-(IC1-PA4)") (class "Default")
      (node (ref "IC1") (pin "20") (pinfunction "PA4_20") (pintype "bidirectional"))
      (node (ref "R40") (pin "2") (pinfunction "2_2") (pintype "passive"))
    )
    (net (code "60") (name "Net-(IC1-PA5)") (class "Default")
      (node (ref "IC1") (pin "21") (pinfunction "PA5_21") (pintype "bidirectional"))
      (node (ref "R41") (pin "2") (pinfunction "2_2") (pintype "passive"))
    )
    (net (code "61") (name "Net-(IC1-PA6)") (class "Default")
      (node (ref "IC1") (pin "22") (pinfunction "PA6_22") (pintype "bidirectional"))
      (node (ref "R42") (pin "2") (pinfunction "2_2") (pintype "passive"))
    )
    (net (code "62") (name "Net-(IC1-PA7)") (class "Default")
      (node (ref "IC1") (pin "23") (pinfunction "PA7_23") (pintype "bidirectional"))
      (node (ref "R43") (pin "2") (pinfunction "2_2") (pintype "passive"))
    )
    (net (code "63") (name "Net-(IC2-BYPASS)") (class "Default")
      (node (ref "C4") (pin "2") (pinfunction "2_2") (pintype "passive"))
      (node (ref "IC2") (pin "4") (pinfunction "BYPASS_4") (pintype "bidirectional"))
    )
    (net (code "64") (name "Net-(IC2-VO)") (class "Default")
      (node (ref "IC2") (pin "5") (pinfunction "VO_5") (pintype "bidirectional"))
      (node (ref "R34") (pin "2") (pinfunction "2_2") (pintype "passive"))
    )
    (net (code "65") (name "Net-(IC3-BYPASS)") (class "Default")
      (node (ref "C9") (pin "2") (pinfunction "2_2") (pintype "passive"))
      (node (ref "IC3") (pin "4") (pinfunction "BYPASS_4") (pintype "bidirectional"))
    )
    (net (code "66") (name "Net-(IC3-VO)") (class "Default")
      (node (ref "IC3") (pin "5") (pinfunction "VO_5") (pintype "bidirectional"))
      (node (ref "R35") (pin "2") (pinfunction "2_2") (pintype "passive"))
    )
    (net (code "67") (name "Net-(IC4-RATE)") (class "Default")
      (node (ref "10HZ") (pin "1") (pinfunction "1_1") (pintype "passive"))
      (node (ref "80HZ") (pin "1") (pinfunction "1_1") (pintype "passive"))
      (node (ref "IC4") (pin "15") (pinfunction "RATE_15") (pintype "bidirectional"))
    )
    (net (code "68") (name "Net-(IC4-VBG)") (class "Default")
      (node (ref "C17") (pin "2") (pinfunction "2_2") (pintype "passive"))
      (node (ref "IC4") (pin "6") (pinfunction "VBG_6") (pintype "bidirectional"))
    )
    (net (code "69") (name "Net-(IC5-1OUT)") (class "Default")
      (node (ref "IC5") (pin "1") (pinfunction "1OUT_1") (pintype "bidirectional"))
      (node (ref "R15") (pin "2") (pinfunction "2_2") (pintype "passive"))
    )
    (net (code "70") (name "Net-(IC5-2OUT)") (class "Default")
      (node (ref "IC5") (pin "7") (pinfunction "2OUT_7") (pintype "bidirectional"))
      (node (ref "R16") (pin "1") (pinfunction "1_1") (pintype "passive"))
    )
    (net (code "71") (name "Net-(J13-Pad2)") (class "Default")
      (node (ref "J13") (pin "2") (pinfunction "2_2") (pintype "passive"))
      (node (ref "R44") (pin "1") (pinfunction "1_1") (pintype "passive"))
    )
    (net (code "72") (name "Net-(J13-Pad3)") (class "Default")
      (node (ref "J13") (pin "3") (pinfunction "3_3") (pintype "passive"))
      (node (ref "R45") (pin "1") (pinfunction "1_1") (pintype "passive"))
    )
    (net (code "73") (name "Net-(J13-Pad4)") (class "Default")
      (node (ref "J13") (pin "4") (pinfunction "4_4") (pintype "passive"))
      (node (ref "R46") (pin "1") (pinfunction "1_1") (pintype "passive"))
    )
    (net (code "74") (name "Net-(J14-Pad1)") (class "Default")
      (node (ref "J14") (pin "1") (pinfunction "1_1") (pintype "passive"))
      (node (ref "R24") (pin "2") (pinfunction "2_2") (pintype "passive"))
    )
    (net (code "75") (name "Net-(J15-Pad1)") (class "Default")
      (node (ref "J15") (pin "1") (pinfunction "1_1") (pintype "passive"))
      (node (ref "R25") (pin "2") (pinfunction "2_2") (pintype "passive"))
    )
    (net (code "76") (name "Net-(J16-Pad1)") (class "Default")
      (node (ref "J16") (pin "1") (pinfunction "1_1") (pintype "passive"))
      (node (ref "R26") (pin "1") (pinfunction "1_1") (pintype "passive"))
    )
    (net (code "77") (name "Net-(LED1-PadA)") (class "Default")
      (node (ref "LED1") (pin "A") (pinfunction "A_A") (pintype "passive"))
      (node (ref "R15") (pin "1") (pinfunction "1_1") (pintype "passive"))
    )
    (net (code "78") (name "Net-(LED2-PadA)") (class "Default")
      (node (ref "LED2") (pin "A") (pinfunction "A_A") (pintype "passive"))
      (node (ref "R16") (pin "2") (pinfunction "2_2") (pintype "passive"))
    )
    (net (code "79") (name "Net-(LED3-PadA)") (class "Default")
      (node (ref "LED3") (pin "A") (pinfunction "A_A") (pintype "passive"))
      (node (ref "R24") (pin "1") (pinfunction "1_1") (pintype "passive"))
    )
    (net (code "80") (name "Net-(LED4-PadA)") (class "Default")
      (node (ref "LED4") (pin "A") (pinfunction "A_A") (pintype "passive"))
      (node (ref "R25") (pin "1") (pinfunction "1_1") (pintype "passive"))
    )
    (net (code "81") (name "Net-(LED6-PadA)") (class "Default")
      (node (ref "LED6") (pin "A") (pinfunction "A_A") (pintype "passive"))
      (node (ref "R26") (pin "2") (pinfunction "2_2") (pintype "passive"))
    )
    (net (code "82") (name "Net-(NRST-2-Pad3)") (class "Default")
      (node (ref "NRST") (pin "3") (pinfunction "2_3") (pintype "passive"))
      (node (ref "NRST") (pin "4") (pinfunction "2_4") (pintype "passive"))
      (node (ref "R13") (pin "1") (pinfunction "1_1") (pintype "passive"))
    )
    (net (code "83") (name "Net-(U1-PROG)") (class "Default")
      (node (ref "R17") (pin "1") (pinfunction "1_1") (pintype "passive"))
      (node (ref "U1") (pin "5") (pinfunction "PROG_5") (pintype "input"))
    )
    (net (code "84") (name "RD") (class "Default")
      (node (ref "SV1") (pin "15") (pinfunction "15_15") (pintype "passive"))
    )
    (net (code "85") (name "SD_CS") (class "Default")
      (node (ref "IC1") (pin "40") (pinfunction "PC9_40") (pintype "bidirectional"))
      (node (ref "R9") (pin "1") (pinfunction "1_1") (pintype "passive"))
      (node (ref "SV2") (pin "2") (pinfunction "2_2") (pintype "passive"))
    )
    (net (code "86") (name "SD_DET") (class "Default")
      (node (ref "IC1") (pin "41") (pinfunction "PA8_41") (pintype "bidirectional"))
      (node (ref "SV2") (pin "1") (pinfunction "1_1") (pintype "passive"))
    )
    (net (code "87") (name "STAT") (class "Default")
      (node (ref "IC5") (pin "3") (pinfunction "1IN+_3") (pintype "bidirectional"))
      (node (ref "IC5") (pin "6") (pinfunction "2IN-_6") (pintype "bidirectional"))
      (node (ref "R18") (pin "1") (pinfunction "1_1") (pintype "passive"))
      (node (ref "R19") (pin "2") (pinfunction "2_2") (pintype "passive"))
      (node (ref "U1") (pin "1") (pinfunction "STAT_1") (pintype "output"))
    )
    (net (code "88") (name "SWCLK") (class "Default")
      (node (ref "IC1") (pin "49") (pinfunction "PA14_49") (pintype "bidirectional"))
      (node (ref "J17") (pin "1") (pinfunction "1_1") (pintype "passive"))
      (node (ref "R2") (pin "2") (pinfunction "2_2") (pintype "passive"))
    )
    (net (code "89") (name "SWDIO") (class "Default")
      (node (ref "IC1") (pin "46") (pinfunction "PA13_46") (pintype "bidirectional"))
      (node (ref "J17") (pin "2") (pinfunction "2_2") (pintype "passive"))
      (node (ref "R1") (pin "1") (pinfunction "1_1") (pintype "passive"))
    )
    (net (code "90") (name "TFT_CS") (class "Default")
      (node (ref "IC1") (pin "33") (pinfunction "PB12_33") (pintype "bidirectional"))
      (node (ref "R10") (pin "1") (pinfunction "1_1") (pintype "passive"))
      (node (ref "SPI") (pin "4") (pinfunction "4_4") (pintype "passive"))
      (node (ref "SV1") (pin "18") (pinfunction "18_18") (pintype "passive"))
      (node (ref "SV2") (pin "14") (pinfunction "14_14") (pintype "passive"))
    )
    (net (code "91") (name "TFT_DC") (class "Default")
      (node (ref "IC1") (pin "37") (pinfunction "PC6_37") (pintype "bidirectional"))
      (node (ref "SPI") (pin "5") (pinfunction "5_5") (pintype "passive"))
      (node (ref "SV1") (pin "17") (pinfunction "17_17") (pintype "passive"))
      (node (ref "SV2") (pin "13") (pinfunction "13_13") (pintype "passive"))
    )
    (net (code "92") (name "TFT_MISO") (class "Default")
      (node (ref "IC1") (pin "35") (pinfunction "PB14_35") (pintype "bidirectional"))
      (node (ref "SPI") (pin "2") (pinfunction "2_2") (pintype "passive"))
      (node (ref "SV2") (pin "16") (pinfunction "16_16") (pintype "passive"))
    )
    (net (code "93") (name "TFT_MOSI") (class "Default")
      (node (ref "IC1") (pin "36") (pinfunction "PB15_36") (pintype "bidirectional"))
      (node (ref "SPI") (pin "3") (pinfunction "3_3") (pintype "passive"))
      (node (ref "SV2") (pin "15") (pinfunction "15_15") (pintype "passive"))
    )
    (net (code "94") (name "TFT_NRST") (class "Default")
      (node (ref "IC1") (pin "38") (pinfunction "PC7_38") (pintype "bidirectional"))
      (node (ref "SV1") (pin "14") (pinfunction "14_14") (pintype "passive"))
      (node (ref "SV2") (pin "12") (pinfunction "12_12") (pintype "passive"))
    )
    (net (code "95") (name "TFT_SCK") (class "Default")
      (node (ref "IC1") (pin "34") (pinfunction "PB13_34") (pintype "bidirectional"))
      (node (ref "SPI") (pin "1") (pinfunction "1_1") (pintype "passive"))
      (node (ref "SV2") (pin "17") (pinfunction "17_17") (pintype "passive"))
    )
    (net (code "96") (name "VBATT") (class "Default")
      (node (ref "C1") (pin "1") (pinfunction "1_1") (pintype "passive"))
      (node (ref "C10") (pin "1") (pinfunction "1_1") (pintype "passive"))
      (node (ref "C20") (pin "1") (pinfunction "1_1") (pintype "passive"))
      (node (ref "C23") (pin "1") (pinfunction "1_1") (pintype "passive"))
      (node (ref "C5") (pin "1") (pinfunction "1_1") (pintype "passive"))
      (node (ref "C6") (pin "1") (pinfunction "1_1") (pintype "passive"))
      (node (ref "IC2") (pin "1") (pinfunction "V1_1") (pintype "bidirectional"))
      (node (ref "IC3") (pin "1") (pinfunction "V1_1") (pintype "bidirectional"))
      (node (ref "PWR") (pin "2") (pinfunction "2_2") (pintype "passive"))
      (node (ref "U1") (pin "3") (pinfunction "VBAT_3") (pintype "power_in"))
    )
    (net (code "97") (name "VCAP1") (class "Default")
      (node (ref "C11") (pin "1") (pinfunction "1_1") (pintype "passive"))
      (node (ref "C12") (pin "1") (pinfunction "1_1") (pintype "passive"))
      (node (ref "IC1") (pin "30") (pinfunction "VCAP1_30") (pintype "bidirectional"))
    )
    (net (code "98") (name "VDD") (class "Default")
      (node (ref "C15") (pin "1") (pinfunction "1_1") (pintype "passive"))
      (node (ref "C16") (pin "1") (pinfunction "1_1") (pintype "passive"))
      (node (ref "C29") (pin "1") (pinfunction "1_1") (pintype "passive"))
      (node (ref "C33") (pin "1") (pinfunction "1_1") (pintype "passive"))
      (node (ref "IC4") (pin "1") (pinfunction "VSUP_1") (pintype "bidirectional"))
      (node (ref "IC4") (pin "16") (pinfunction "DVDD_16") (pintype "bidirectional"))
      (node (ref "J16") (pin "2") (pinfunction "2_2") (pintype "passive"))
      (node (ref "J5") (pin "4") (pinfunction "4_4") (pintype "passive"))
      (node (ref "Q1") (pin "1") (pinfunction "E_1") (pintype "bidirectional"))
      (node (ref "R28") (pin "1") (pinfunction "1_1") (pintype "passive"))
      (node (ref "U$8") (pin "1") (pinfunction "1_1") (pintype "bidirectional"))
    )
    (net (code "99") (name "VDDA") (class "Default")
      (node (ref "C7") (pin "1") (pinfunction "1_1") (pintype "passive"))
      (node (ref "C8") (pin "1") (pinfunction "1_1") (pintype "passive"))
      (node (ref "IC1") (pin "13") (pinfunction "VDDA/VREF+_13") (pintype "bidirectional"))
      (node (ref "J15") (pin "2") (pinfunction "2_2") (pintype "passive"))
      (node (ref "R35") (pin "1") (pinfunction "1_1") (pintype "passive"))
      (node (ref "U$6") (pin "1") (pinfunction "1_1") (pintype "bidirectional"))
    )
    (net (code "100") (name "VIN") (class "Default")
      (node (ref "J12") (pin "1") (pinfunction "1_1") (pintype "bidirectional"))
      (node (ref "PWR") (pin "1") (pinfunction "1_1") (pintype "passive"))
    )
    (net (code "101") (name "V_BASE") (class "Default")
      (node (ref "IC4") (pin "2") (pinfunction "BASE_2") (pintype "bidirectional"))
      (node (ref "Q1") (pin "2") (pinfunction "B_2") (pintype "bidirectional"))
    )
    (net (code "102") (name "V_FB") (class "Default")
      (node (ref "IC4") (pin "4") (pinfunction "VFB_4") (pintype "bidirectional"))
      (node (ref "R3") (pin "1") (pinfunction "1_1") (pintype "passive"))
      (node (ref "R4") (pin "2") (pinfunction "2_2") (pintype "passive"))
    )
    (net (code "103") (name "V_HI") (class "Default")
      (node (ref "IC5") (pin "2") (pinfunction "1IN-_2") (pintype "bidirectional"))
      (node (ref "R21") (pin "1") (pinfunction "1_1") (pintype "passive"))
      (node (ref "R22") (pin "2") (pinfunction "2_2") (pintype "passive"))
    )
    (net (code "104") (name "V_LO") (class "Default")
      (node (ref "IC5") (pin "5") (pinfunction "2IN+_5") (pintype "bidirectional"))
      (node (ref "R20") (pin "1") (pinfunction "1_1") (pintype "passive"))
      (node (ref "R23") (pin "2") (pinfunction "2_2") (pintype "passive"))
    )
    (net (code "105") (name "WR") (class "Default")
      (node (ref "SV1") (pin "16") (pinfunction "16_16") (pintype "passive"))
    )
    (net (code "106") (name "X+") (class "Default")
      (node (ref "IC1") (pin "27") (pinfunction "PB1_27") (pintype "bidirectional"))
      (node (ref "J11") (pin "2") (pinfunction "2_2") (pintype "passive"))
      (node (ref "SV2") (pin "9") (pinfunction "9_9") (pintype "passive"))
    )
    (net (code "107") (name "X+_NC") (class "Default")
      (node (ref "SV1") (pin "12") (pinfunction "12_12") (pintype "passive"))
    )
    (net (code "108") (name "X-") (class "Default")
      (node (ref "IC1") (pin "24") (pinfunction "PC4_24") (pintype "bidirectional"))
      (node (ref "J11") (pin "4") (pinfunction "4_4") (pintype "passive"))
      (node (ref "SV2") (pin "7") (pinfunction "7_7") (pintype "passive"))
    )
    (net (code "109") (name "X-_NC") (class "Default")
      (node (ref "SV1") (pin "10") (pinfunction "10_10") (pintype "passive"))
    )
    (net (code "110") (name "Y+") (class "Default")
      (node (ref "IC1") (pin "26") (pinfunction "PB0_26") (pintype "bidirectional"))
      (node (ref "J11") (pin "1") (pinfunction "1_1") (pintype "passive"))
      (node (ref "SV2") (pin "10") (pinfunction "10_10") (pintype "passive"))
    )
    (net (code "111") (name "Y+_NC") (class "Default")
      (node (ref "SV1") (pin "11") (pinfunction "11_11") (pintype "passive"))
    )
    (net (code "112") (name "Y-") (class "Default")
      (node (ref "IC1") (pin "25") (pinfunction "PC5_25") (pintype "bidirectional"))
      (node (ref "J11") (pin "3") (pinfunction "3_3") (pintype "passive"))
      (node (ref "SV2") (pin "8") (pinfunction "8_8") (pintype "passive"))
    )
    (net (code "113") (name "Y-_NC") (class "Default")
      (node (ref "SV1") (pin "9") (pinfunction "9_9") (pintype "passive"))
    )
    (net (code "114") (name "unconnected-(IC1-PA0-Pad14)") (class "Default")
      (node (ref "IC1") (pin "14") (pinfunction "PA0_14") (pintype "bidirectional"))
    )
    (net (code "115") (name "unconnected-(IC1-PA1-Pad15)") (class "Default")
      (node (ref "IC1") (pin "15") (pinfunction "PA1_15") (pintype "bidirectional"))
    )
    (net (code "116") (name "unconnected-(IC1-PA2-Pad16)") (class "Default")
      (node (ref "IC1") (pin "16") (pinfunction "PA2_16") (pintype "bidirectional"))
    )
    (net (code "117") (name "unconnected-(IC1-PA3-Pad17)") (class "Default")
      (node (ref "IC1") (pin "17") (pinfunction "PA3_17") (pintype "bidirectional"))
    )
    (net (code "118") (name "unconnected-(IC1-PA15-Pad50)") (class "Default")
      (node (ref "IC1") (pin "50") (pinfunction "PA15_50") (pintype "bidirectional"))
    )
    (net (code "119") (name "unconnected-(IC1-PB2-Pad28)") (class "Default")
      (node (ref "IC1") (pin "28") (pinfunction "PB2_28") (pintype "bidirectional"))
    )
    (net (code "120") (name "unconnected-(IC1-PB10-Pad29)") (class "Default")
      (node (ref "IC1") (pin "29") (pinfunction "PB10_29") (pintype "bidirectional"))
    )
    (net (code "121") (name "unconnected-(IC1-PC13-Pad2)") (class "Default")
      (node (ref "IC1") (pin "2") (pinfunction "PC13_2") (pintype "bidirectional"))
    )
    (net (code "122") (name "unconnected-(IC1-PC14-_OSC32_IN-Pad3)") (class "Default")
      (node (ref "IC1") (pin "3") (pinfunction "PC14-_OSC32_IN_3") (pintype "bidirectional"))
    )
    (net (code "123") (name "unconnected-(IC1-PC15-OSC32_OUT-Pad4)") (class "Default")
      (node (ref "IC1") (pin "4") (pinfunction "PC15-OSC32_OUT_4") (pintype "bidirectional"))
    )
    (net (code "124") (name "unconnected-(IC1-PD2-Pad54)") (class "Default")
      (node (ref "IC1") (pin "54") (pinfunction "PD2_54") (pintype "bidirectional"))
    )
    (net (code "125") (name "unconnected-(IC4-XO-Pad13)") (class "Default")
      (node (ref "IC4") (pin "13") (pinfunction "XO_13") (pintype "bidirectional"))
    )
  )
)
